# CapProtector.net
KiCad netlist of a schematic drawn in Altium Designer
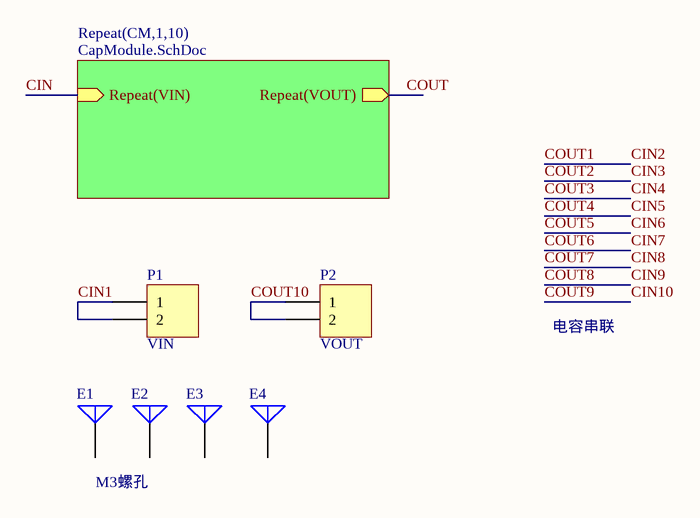
[diagram p0: CapProtector.SchDoc]

(export (version "E")
  (design (tool "Eeschema 10.0.6"))
  (components
    (comp (ref "E1")
      (value "Antenna")
      (footprint "M3x4_N")
      (description "Generic Antenna")
      (fields (field (name "PUBLISHER") "Altium Limited"))
      (libsource (lib "Miscellaneous Devices") (part "Antenna"))
    )
    (comp (ref "E2")
      (value "Antenna")
      (footprint "M3x4_N")
      (description "Generic Antenna")
      (fields (field (name "PUBLISHER") "Altium Limited"))
      (libsource (lib "Miscellaneous Devices") (part "Antenna"))
    )
    (comp (ref "E3")
      (value "Antenna")
      (footprint "M3x4_N")
      (description "Generic Antenna")
      (fields (field (name "PUBLISHER") "Altium Limited"))
      (libsource (lib "Miscellaneous Devices") (part "Antenna"))
    )
    (comp (ref "E4")
      (value "Antenna")
      (footprint "M3x4_N")
      (description "Generic Antenna")
      (fields (field (name "PUBLISHER") "Altium Limited"))
      (libsource (lib "Miscellaneous Devices") (part "Antenna"))
    )
    (comp (ref "P1")
      (value "VIN")
      (footprint "XT30U-M")
      (description "Header, 2-Pin")
      (fields (field (name "PUBLISHER") "Altium Limited"))
      (libsource (lib "Miscellaneous Connectors") (part "Header 2"))
    )
    (comp (ref "P2")
      (value "VOUT")
      (footprint "XT30U-F")
      (description "Header, 2-Pin")
      (fields (field (name "PUBLISHER") "Altium Limited"))
      (libsource (lib "Miscellaneous Connectors") (part "Header 2"))
    )
  )
  (nets
    (net (code "2") (name "/CIN1") (class "Default")
      (node (ref "P1") (pin "1") (pinfunction "1_1") (pintype "passive"))
      (node (ref "P1") (pin "2") (pinfunction "2_2") (pintype "passive"))
    )
    (net (code "13") (name "/COUT10") (class "Default")
      (node (ref "P2") (pin "1") (pinfunction "1_1") (pintype "passive"))
      (node (ref "P2") (pin "2") (pinfunction "2_2") (pintype "passive"))
    )
    (net (code "14") (name "unconnected-(E1-A-Pad1)") (class "Default")
      (node (ref "E1") (pin "1") (pinfunction "A_1") (pintype "passive"))
    )
    (net (code "15") (name "unconnected-(E2-A-Pad1)") (class "Default")
      (node (ref "E2") (pin "1") (pinfunction "A_1") (pintype "passive"))
    )
    (net (code "16") (name "unconnected-(E3-A-Pad1)") (class "Default")
      (node (ref "E3") (pin "1") (pinfunction "A_1") (pintype "passive"))
    )
    (net (code "17") (name "unconnected-(E4-A-Pad1)") (class "Default")
      (node (ref "E4") (pin "1") (pinfunction "A_1") (pintype "passive"))
    )
  )
)
